# Sheet1.net
KiCad netlist of a schematic drawn in Altium Designer
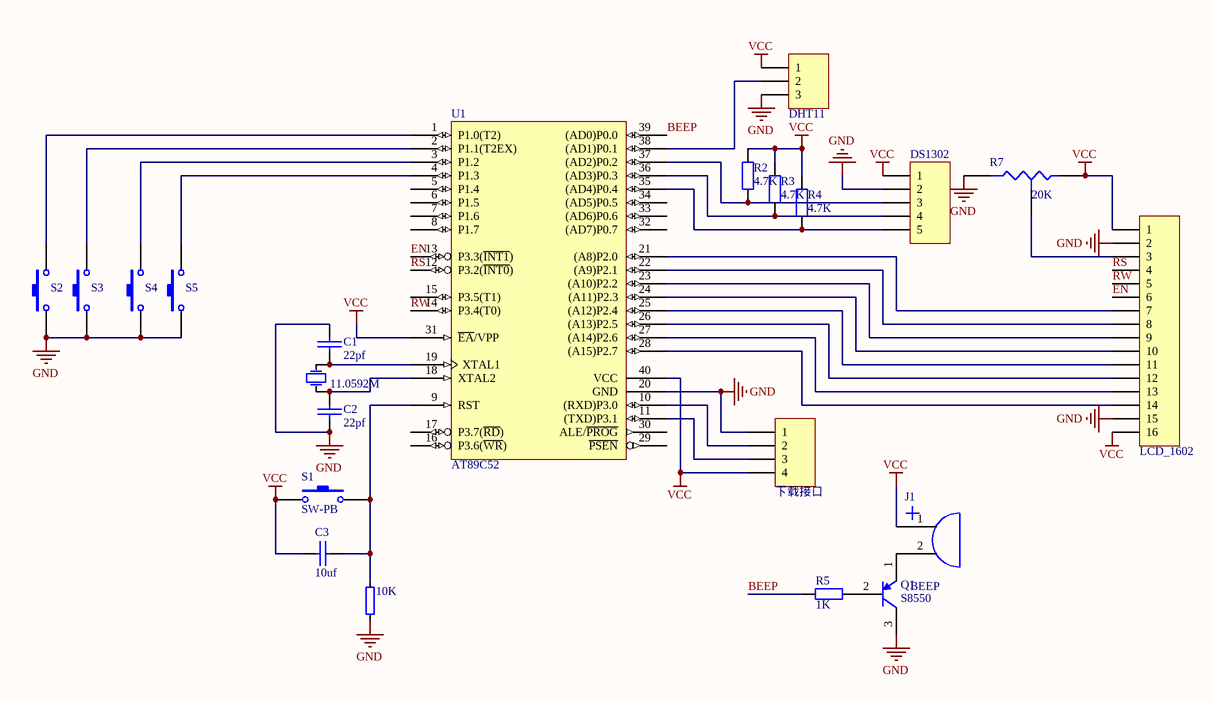
[diagram p0: Sheet1.SchDoc]

(export (version "E")
  (design (tool "Eeschema 10.0.6"))
  (components
    (comp (ref "10K") (value "R") (footprint "0402") (libsource (lib "MCU_ZGZ_Library") (part "R")))
    (comp (ref "C1") (value "22pf") (footprint "0402") (libsource (lib "MCU_ZGZ_Library") (part "C")))
    (comp (ref "C2") (value "22pf") (footprint "0402") (libsource (lib "MCU_ZGZ_Library") (part "C")))
    (comp (ref "C3") (value "10uf") (footprint "0402") (libsource (lib "MCU_ZGZ_Library") (part "C")))
    (comp (ref "DHT11")
      (value "Header 3")
      (footprint "HDR3X1_A")
      (description "接插件")
      (fields (field (name "PUBLISHER") "Altium Limited"))
      (libsource (lib "Fszhang") (part "Header 3"))
    )
    (comp (ref "DS1302")
      (value "Header 5")
      (footprint "HDR1X5")
      (description "Header, 5-Pin")
      (fields (field (name "PUBLISHER") "Altium Limited"))
      (libsource (lib "Miscellaneous Connectors") (part "Header 5"))
    )
    (comp (ref "J1")
      (value "BEEP")
      (footprint "Beep")
      (description "蜂鸣器")
      (libsource (lib "Fszhang") (part "BEEP"))
    )
    (comp (ref "P2")
      (value "LCD_1602")
      (footprint "HDR1X16")
      (description "Header, 16-Pin")
      (fields (field (name "PUBLISHER") "Altium Limited"))
      (libsource (lib "Miscellaneous Connectors") (part "Header 16"))
    )
    (comp (ref "Q1")
      (value "S8550")
      (footprint "TO-92A")
      (description "PNP三极管")
      (fields (field (name "PUBLISHER") "Altium Limited"))
      (libsource (lib "Fszhang") (part "S8550"))
    )
    (comp (ref "R2")
      (value "4.7K")
      (footprint "AXIAL-0.4")
      (description "Resistor")
      (fields (field (name "Comment") "Res2") (field (name "PUBLISHER") "Altium Limited"))
      (libsource (lib "Miscellaneous Devices") (part "Res2"))
    )
    (comp (ref "R3")
      (value "4.7K")
      (footprint "AXIAL-0.4")
      (description "Resistor")
      (fields (field (name "Comment") "Res2") (field (name "PUBLISHER") "Altium Limited"))
      (libsource (lib "Miscellaneous Devices") (part "Res2"))
    )
    (comp (ref "R4")
      (value "4.7K")
      (footprint "AXIAL-0.4")
      (description "Resistor")
      (fields (field (name "Comment") "Res2") (field (name "PUBLISHER") "Altium Limited"))
      (libsource (lib "Miscellaneous Devices") (part "Res2"))
    )
    (comp (ref "R5")
      (value "1K")
      (footprint "AXIAL-0.4")
      (description "Resistor")
      (fields (field (name "Comment") "Res2") (field (name "PUBLISHER") "Altium Limited"))
      (libsource (lib "") (part "Res2_1"))
    )
    (comp (ref "R7")
      (value "20K")
      (footprint "VR3")
      (description "Tapped Resistor")
      (fields (field (name "Comment") "Res Tap") (field (name "PUBLISHER") "Altium Limited"))
      (libsource (lib "Miscellaneous Devices") (part "Res Tap"))
    )
    (comp (ref "S1")
      (value "SW-PB")
      (footprint "SW_PB2_A1")
      (description "微动开关")
      (fields (field (name "PUBLISHER") "Altium Limited"))
      (libsource (lib "Fszhang") (part "SW-PB"))
    )
    (comp (ref "S2")
      (value "SW-PB")
      (footprint "SW_PB2_A1")
      (description "微动开关")
      (fields (field (name "PUBLISHER") "Altium Limited"))
      (libsource (lib "Fszhang") (part "SW-PB"))
    )
    (comp (ref "S3")
      (value "SW-PB")
      (footprint "SW_PB2_A1")
      (description "微动开关")
      (fields (field (name "PUBLISHER") "Altium Limited"))
      (libsource (lib "Fszhang") (part "SW-PB"))
    )
    (comp (ref "S4")
      (value "SW-PB")
      (footprint "SW_PB2_A1")
      (description "微动开关")
      (fields (field (name "PUBLISHER") "Altium Limited"))
      (libsource (lib "Fszhang") (part "SW-PB"))
    )
    (comp (ref "S5")
      (value "SW-PB")
      (footprint "SW_PB2_A1")
      (description "微动开关")
      (fields (field (name "PUBLISHER") "Altium Limited"))
      (libsource (lib "Fszhang") (part "SW-PB"))
    )
    (comp (ref "U1")
      (value "AT89C52")
      (footprint "DIP-40")
      (description "8-Bit Microcontroller with 8K Flash ROM")
      (libsource (lib "单片机8051") (part "AT89C52"))
    )
    (comp (ref "Y1")
      (value "11.0592M")
      (footprint "X-HC49U")
      (description "晶振")
      (fields (field (name "Comment") "XTAL") (field (name "PUBLISHER") "Altium Limited"))
      (libsource (lib "Fszhang") (part "XTAL"))
    )
    (comp (ref "下载接口")
      (value "Header 4")
      (footprint "HDR4X1_A")
      (description "接插件")
      (fields (field (name "PUBLISHER") "Altium Limited"))
      (libsource (lib "Fszhang") (part "Header 4"))
    )
  )
  (nets
    (net (code "1") (name "/BEEP") (class "Default")
      (node (ref "R5") (pin "2") (pinfunction "2_2") (pintype "passive"))
      (node (ref "U1") (pin "39") (pinfunction "(AD0)P0.0_39") (pintype "bidirectional"))
    )
    (net (code "2") (name "/EN") (class "Default")
      (node (ref "P2") (pin "6") (pinfunction "6_6") (pintype "passive"))
      (node (ref "U1") (pin "13") (pinfunction "P3.3(~{INT1})_13") (pintype "bidirectional"))
    )
    (net (code "3") (name "/RS") (class "Default")
      (node (ref "P2") (pin "4") (pinfunction "4_4") (pintype "passive"))
      (node (ref "U1") (pin "12") (pinfunction "P3.2(~{INT0})_12") (pintype "bidirectional"))
    )
    (net (code "4") (name "/RW") (class "Default")
      (node (ref "P2") (pin "5") (pinfunction "5_5") (pintype "passive"))
      (node (ref "U1") (pin "14") (pinfunction "P3.4(T0)_14") (pintype "bidirectional"))
    )
    (net (code "5") (name "GND") (class "Default")
      (node (ref "10K") (pin "1") (pinfunction "1_1") (pintype "passive"))
      (node (ref "C1") (pin "2") (pinfunction "2_2") (pintype "passive"))
      (node (ref "C2") (pin "1") (pinfunction "1_1") (pintype "passive"))
      (node (ref "DHT11") (pin "3") (pinfunction "3_3") (pintype "passive"))
      (node (ref "DS1302") (pin "2") (pinfunction "2_2") (pintype "passive"))
      (node (ref "P2") (pin "15") (pinfunction "15_15") (pintype "passive"))
      (node (ref "P2") (pin "2") (pinfunction "2_2") (pintype "passive"))
      (node (ref "Q1") (pin "3") (pinfunction "C_3") (pintype "passive"))
      (node (ref "R7") (pin "2") (pinfunction "B_2") (pintype "passive"))
      (node (ref "S2") (pin "1") (pinfunction "1_1") (pintype "passive"))
      (node (ref "S3") (pin "1") (pinfunction "1_1") (pintype "passive"))
      (node (ref "S4") (pin "1") (pinfunction "1_1") (pintype "passive"))
      (node (ref "S5") (pin "1") (pinfunction "1_1") (pintype "passive"))
      (node (ref "U1") (pin "20") (pinfunction "GND_20") (pintype "power_in"))
      (node (ref "下载接口") (pin "1") (pinfunction "1_1") (pintype "passive"))
    )
    (net (code "6") (name "Net-(J1-1)") (class "Default")
      (node (ref "J1") (pin "2") (pinfunction "1_2") (pintype "passive"))
      (node (ref "Q1") (pin "1") (pinfunction "E_1") (pintype "passive"))
    )
    (net (code "7") (name "Net-(Q1-B)") (class "Default")
      (node (ref "Q1") (pin "2") (pinfunction "B_2") (pintype "passive"))
      (node (ref "R5") (pin "1") (pinfunction "1_1") (pintype "passive"))
    )
    (net (code "8") (name "Net-(R7-TAP)") (class "Default")
      (node (ref "P2") (pin "3") (pinfunction "3_3") (pintype "passive"))
      (node (ref "R7") (pin "3") (pinfunction "TAP_3") (pintype "passive"))
    )
    (net (code "9") (name "Net-(U1-(A8)P2.0)") (class "Default")
      (node (ref "P2") (pin "7") (pinfunction "7_7") (pintype "passive"))
      (node (ref "U1") (pin "21") (pinfunction "(A8)P2.0_21") (pintype "bidirectional"))
    )
    (net (code "10") (name "Net-(U1-(A9)P2.1)") (class "Default")
      (node (ref "P2") (pin "8") (pinfunction "8_8") (pintype "passive"))
      (node (ref "U1") (pin "22") (pinfunction "(A9)P2.1_22") (pintype "bidirectional"))
    )
    (net (code "11") (name "Net-(U1-(A10)P2.2)") (class "Default")
      (node (ref "P2") (pin "9") (pinfunction "9_9") (pintype "passive"))
      (node (ref "U1") (pin "23") (pinfunction "(A10)P2.2_23") (pintype "bidirectional"))
    )
    (net (code "12") (name "Net-(U1-(A11)P2.3)") (class "Default")
      (node (ref "P2") (pin "10") (pinfunction "10_10") (pintype "passive"))
      (node (ref "U1") (pin "24") (pinfunction "(A11)P2.3_24") (pintype "bidirectional"))
    )
    (net (code "13") (name "Net-(U1-(A12)P2.4)") (class "Default")
      (node (ref "P2") (pin "11") (pinfunction "11_11") (pintype "passive"))
      (node (ref "U1") (pin "25") (pinfunction "(A12)P2.4_25") (pintype "bidirectional"))
    )
    (net (code "14") (name "Net-(U1-(A13)P2.5)") (class "Default")
      (node (ref "P2") (pin "12") (pinfunction "12_12") (pintype "passive"))
      (node (ref "U1") (pin "26") (pinfunction "(A13)P2.5_26") (pintype "bidirectional"))
    )
    (net (code "15") (name "Net-(U1-(A14)P2.6)") (class "Default")
      (node (ref "P2") (pin "13") (pinfunction "13_13") (pintype "passive"))
      (node (ref "U1") (pin "27") (pinfunction "(A14)P2.6_27") (pintype "bidirectional"))
    )
    (net (code "16") (name "Net-(U1-(A15)P2.7)") (class "Default")
      (node (ref "P2") (pin "14") (pinfunction "14_14") (pintype "passive"))
      (node (ref "U1") (pin "28") (pinfunction "(A15)P2.7_28") (pintype "bidirectional"))
    )
    (net (code "17") (name "Net-(U1-(AD1)P0.1)") (class "Default")
      (node (ref "DHT11") (pin "2") (pinfunction "2_2") (pintype "passive"))
      (node (ref "U1") (pin "38") (pinfunction "(AD1)P0.1_38") (pintype "bidirectional"))
    )
    (net (code "18") (name "Net-(U1-(AD2)P0.2)") (class "Default")
      (node (ref "DS1302") (pin "3") (pinfunction "3_3") (pintype "passive"))
      (node (ref "R2") (pin "1") (pinfunction "1_1") (pintype "passive"))
      (node (ref "U1") (pin "37") (pinfunction "(AD2)P0.2_37") (pintype "bidirectional"))
    )
    (net (code "19") (name "Net-(U1-(AD3)P0.3)") (class "Default")
      (node (ref "DS1302") (pin "4") (pinfunction "4_4") (pintype "passive"))
      (node (ref "R3") (pin "1") (pinfunction "1_1") (pintype "passive"))
      (node (ref "U1") (pin "36") (pinfunction "(AD3)P0.3_36") (pintype "bidirectional"))
    )
    (net (code "20") (name "Net-(U1-(AD4)P0.4)") (class "Default")
      (node (ref "DS1302") (pin "5") (pinfunction "5_5") (pintype "passive"))
      (node (ref "R4") (pin "1") (pinfunction "1_1") (pintype "passive"))
      (node (ref "U1") (pin "35") (pinfunction "(AD4)P0.4_35") (pintype "bidirectional"))
    )
    (net (code "21") (name "Net-(U1-(RXD)P3.0)") (class "Default")
      (node (ref "U1") (pin "10") (pinfunction "(RXD)P3.0_10") (pintype "bidirectional"))
      (node (ref "下载接口") (pin "2") (pinfunction "2_2") (pintype "passive"))
    )
    (net (code "22") (name "Net-(U1-(TXD)P3.1)") (class "Default")
      (node (ref "U1") (pin "11") (pinfunction "(TXD)P3.1_11") (pintype "bidirectional"))
      (node (ref "下载接口") (pin "3") (pinfunction "3_3") (pintype "passive"))
    )
    (net (code "23") (name "Net-(U1-P1.0(T2))") (class "Default")
      (node (ref "S2") (pin "2") (pinfunction "2_2") (pintype "passive"))
      (node (ref "U1") (pin "1") (pinfunction "P1.0(T2)_1") (pintype "bidirectional"))
    )
    (net (code "24") (name "Net-(U1-P1.1(T2EX))") (class "Default")
      (node (ref "S3") (pin "2") (pinfunction "2_2") (pintype "passive"))
      (node (ref "U1") (pin "2") (pinfunction "P1.1(T2EX)_2") (pintype "bidirectional"))
    )
    (net (code "25") (name "Net-(U1-P1.2)") (class "Default")
      (node (ref "S4") (pin "2") (pinfunction "2_2") (pintype "passive"))
      (node (ref "U1") (pin "3") (pinfunction "P1.2_3") (pintype "bidirectional"))
    )
    (net (code "26") (name "Net-(U1-P1.3)") (class "Default")
      (node (ref "S5") (pin "2") (pinfunction "2_2") (pintype "passive"))
      (node (ref "U1") (pin "4") (pinfunction "P1.3_4") (pintype "bidirectional"))
    )
    (net (code "27") (name "Net-(U1-RST)") (class "Default")
      (node (ref "10K") (pin "2") (pinfunction "2_2") (pintype "passive"))
      (node (ref "C3") (pin "2") (pinfunction "2_2") (pintype "passive"))
      (node (ref "S1") (pin "2") (pinfunction "2_2") (pintype "passive"))
      (node (ref "U1") (pin "9") (pinfunction "RST_9") (pintype "input"))
    )
    (net (code "28") (name "Net-(U1-XTAL1)") (class "Default")
      (node (ref "C1") (pin "1") (pinfunction "1_1") (pintype "passive"))
      (node (ref "U1") (pin "19") (pinfunction "XTAL1_19") (pintype "input"))
      (node (ref "Y1") (pin "2") (pinfunction "OSC2_2") (pintype "passive"))
    )
    (net (code "29") (name "Net-(U1-XTAL2)") (class "Default")
      (node (ref "C2") (pin "2") (pinfunction "2_2") (pintype "passive"))
      (node (ref "U1") (pin "18") (pinfunction "XTAL2_18") (pintype "input"))
      (node (ref "Y1") (pin "1") (pinfunction "OSC1_1") (pintype "passive"))
    )
    (net (code "30") (name "VCC") (class "Default")
      (node (ref "C3") (pin "1") (pinfunction "1_1") (pintype "passive"))
      (node (ref "DHT11") (pin "1") (pinfunction "1_1") (pintype "passive"))
      (node (ref "DS1302") (pin "1") (pinfunction "1_1") (pintype "passive"))
      (node (ref "J1") (pin "1") (pinfunction "0_1") (pintype "passive"))
      (node (ref "P2") (pin "1") (pinfunction "1_1") (pintype "passive"))
      (node (ref "P2") (pin "16") (pinfunction "16_16") (pintype "passive"))
      (node (ref "R2") (pin "2") (pinfunction "2_2") (pintype "passive"))
      (node (ref "R3") (pin "2") (pinfunction "2_2") (pintype "passive"))
      (node (ref "R4") (pin "2") (pinfunction "2_2") (pintype "passive"))
      (node (ref "R7") (pin "1") (pinfunction "A_1") (pintype "passive"))
      (node (ref "S1") (pin "1") (pinfunction "1_1") (pintype "passive"))
      (node (ref "U1") (pin "31") (pinfunction "~{EA}/VPP_31") (pintype "input"))
      (node (ref "U1") (pin "40") (pinfunction "VCC_40") (pintype "power_in"))
      (node (ref "下载接口") (pin "4") (pinfunction "4_4") (pintype "passive"))
    )
    (net (code "31") (name "unconnected-(U1-(AD5)P0.5-Pad34)") (class "Default")
      (node (ref "U1") (pin "34") (pinfunction "(AD5)P0.5_34") (pintype "bidirectional"))
    )
    (net (code "32") (name "unconnected-(U1-(AD6)P0.6-Pad33)") (class "Default")
      (node (ref "U1") (pin "33") (pinfunction "(AD6)P0.6_33") (pintype "bidirectional"))
    )
    (net (code "33") (name "unconnected-(U1-(AD7)P0.7-Pad32)") (class "Default")
      (node (ref "U1") (pin "32") (pinfunction "(AD7)P0.7_32") (pintype "bidirectional"))
    )
    (net (code "34") (name "unconnected-(U1-ALE{slash}~{PROG}-Pad30)") (class "Default")
      (node (ref "U1") (pin "30") (pinfunction "ALE/~{PROG}_30") (pintype "output"))
    )
    (net (code "35") (name "unconnected-(U1-P1.4-Pad5)") (class "Default")
      (node (ref "U1") (pin "5") (pinfunction "P1.4_5") (pintype "bidirectional"))
    )
    (net (code "36") (name "unconnected-(U1-P1.5-Pad6)") (class "Default")
      (node (ref "U1") (pin "6") (pinfunction "P1.5_6") (pintype "bidirectional"))
    )
    (net (code "37") (name "unconnected-(U1-P1.6-Pad7)") (class "Default")
      (node (ref "U1") (pin "7") (pinfunction "P1.6_7") (pintype "bidirectional"))
    )
    (net (code "38") (name "unconnected-(U1-P1.7-Pad8)") (class "Default")
      (node (ref "U1") (pin "8") (pinfunction "P1.7_8") (pintype "bidirectional"))
    )
    (net (code "39") (name "unconnected-(U1-P3.5(T1)-Pad15)") (class "Default")
      (node (ref "U1") (pin "15") (pinfunction "P3.5(T1)_15") (pintype "bidirectional"))
    )
    (net (code "40") (name "unconnected-(U1-P3.6(~{WR})-Pad16)") (class "Default")
      (node (ref "U1") (pin "16") (pinfunction "P3.6(~{WR})_16") (pintype "bidirectional"))
    )
    (net (code "41") (name "unconnected-(U1-P3.7(~{RD})-Pad17)") (class "Default")
      (node (ref "U1") (pin "17") (pinfunction "P3.7(~{RD})_17") (pintype "bidirectional"))
    )
    (net (code "42") (name "unconnected-(U1-~{PSEN}-Pad29)") (class "Default")
      (node (ref "U1") (pin "29") (pinfunction "~{PSEN}_29") (pintype "output"))
    )
  )
)
